# CurrentSenseTest_SCH.net
KiCad netlist of a schematic drawn in Altium Designer
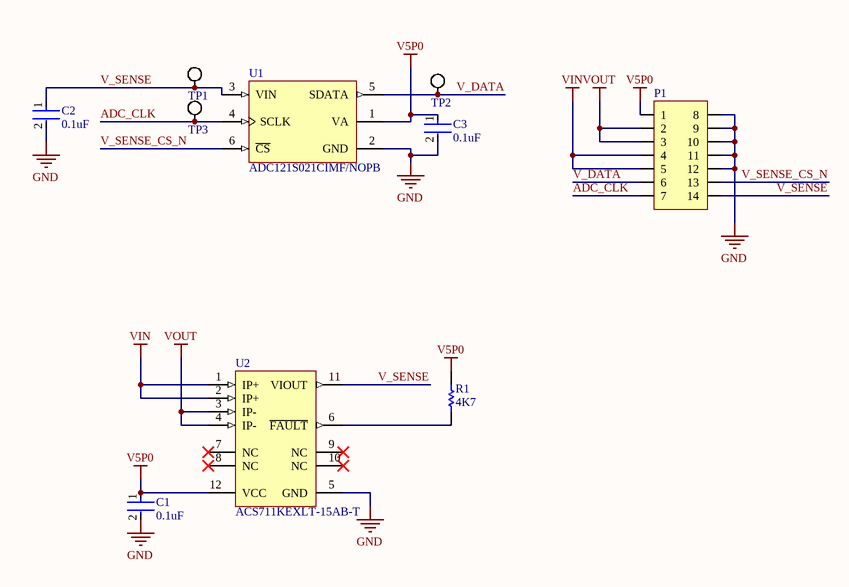
[diagram p0: CurrentSenseTest_SCH.SchDoc]

(export (version "E")
  (design (tool "Eeschema 10.0.6"))
  (components
    (comp (ref "C1")
      (value "0.1uF")
      (footprint "0603")
      (description "CC0603KRX7R9BB104-CAP CER 0.1UF 50V X7R 0603")
      (fields (field (name "MANUFACTURER") "YAGEO") (field (name "VOLTAGE") "50 V"))
      (libsource (lib "TAUV-Lib") (part "0.1uF 0603"))
    )
    (comp (ref "C2")
      (value "0.1uF")
      (footprint "0603")
      (description "CC0603KRX7R9BB104-CAP CER 0.1UF 50V X7R 0603")
      (fields (field (name "MANUFACTURER") "YAGEO") (field (name "VOLTAGE") "50 V"))
      (libsource (lib "TAUV-Lib") (part "0.1uF 0603"))
    )
    (comp (ref "C3")
      (value "0.1uF")
      (footprint "0603")
      (description "CC0603KRX7R9BB104-CAP CER 0.1UF 50V X7R 0603")
      (fields (field (name "MANUFACTURER") "YAGEO") (field (name "VOLTAGE") "50 V"))
      (libsource (lib "TAUV-Lib") (part "0.1uF 0603"))
    )
    (comp (ref "P1")
      (value "14-Pin 2-Row Nano-Fit Right Angle")
      (footprint "MOLEX NANO-FIT 2X7 - Right Angle")
      (description "NanoFit Right Hdr TH DR 14Ckt")
      (fields (field (name "PART NUMBER") "105314-1214") (field (name "MANUFACTURER") "Molex"))
      (libsource (lib "TAUV-Lib") (part "14-Pin 2-Row Nano-Fit Right Angle"))
    )
    (comp (ref "R1")
      (value "4K7")
      (footprint "0603")
      (description "4K7 0.1W 1% 0603 (1608 Metric)  SMD")
      (fields (field (name "POWER") "0.1 W") (field (name "TOLERANCE") "1 %"))
      (libsource (lib "TAUV-Lib") (part "4K7 0603"))
    )
    (comp (ref "TP1")
      (value "Test Point Pad")
      (footprint "Test Point Pad")
      (description "Test point, Pad, 30 mil")
      (libsource (lib "TAUV-Lib") (part "Test Point Pad"))
    )
    (comp (ref "TP2")
      (value "Test Point Pad")
      (footprint "Test Point Pad")
      (description "Test point, Pad, 30 mil")
      (libsource (lib "TAUV-Lib") (part "Test Point Pad"))
    )
    (comp (ref "TP3")
      (value "Test Point Pad")
      (footprint "Test Point Pad")
      (description "Test point, Pad, 30 mil")
      (libsource (lib "TAUV-Lib") (part "Test Point Pad"))
    )
    (comp (ref "U1")
      (value "ADC121S021CIMF/NOPB")
      (footprint "MF06A_L")
      (description "Single Channel, 50 to 200 kSPS, 12-Bit A/D Converter, 6-pin SOT-23, Pb-Free")
      (fields (field (name "MANUFACTURER") "National Semiconductor"))
      (libsource (lib "Altium Content Vault") (part "CON-ADC-ADC101S101CIMF"))
    )
    (comp (ref "U2")
      (value "ACS711KEXLT-15AB-T")
      (footprint "ALEG-EX-12_V")
      (libsource (lib "Altium Content Vault") (part "ALEG-ACS711-QFN-12"))
    )
  )
  (nets
    (net (code "1") (name "/ADC_CLK") (class "Default")
      (node (ref "P1") (pin "7") (pinfunction "7_7") (pintype "passive"))
      (node (ref "TP3") (pin "1") (pinfunction "1_1") (pintype "passive"))
      (node (ref "U1") (pin "4") (pinfunction "SCLK_4") (pintype "input"))
    )
    (net (code "2") (name "/V_DATA") (class "Default")
      (node (ref "P1") (pin "6") (pinfunction "6_6") (pintype "passive"))
      (node (ref "TP2") (pin "1") (pinfunction "1_1") (pintype "passive"))
      (node (ref "U1") (pin "5") (pinfunction "SDATA_5") (pintype "output"))
    )
    (net (code "3") (name "/V_SENSE") (class "Default")
      (node (ref "C2") (pin "1") (pinfunction "1_1") (pintype "passive"))
      (node (ref "P1") (pin "14") (pinfunction "14_14") (pintype "passive"))
      (node (ref "TP1") (pin "1") (pinfunction "1_1") (pintype "passive"))
      (node (ref "U1") (pin "3") (pinfunction "VIN_3") (pintype "input"))
      (node (ref "U2") (pin "11") (pinfunction "VIOUT_11") (pintype "output"))
    )
    (net (code "4") (name "/V_SENSE_CS_N") (class "Default")
      (node (ref "P1") (pin "13") (pinfunction "13_13") (pintype "passive"))
      (node (ref "U1") (pin "6") (pinfunction "~{CS}_6") (pintype "input"))
    )
    (net (code "5") (name "GND") (class "Default")
      (node (ref "C1") (pin "2") (pinfunction "2_2") (pintype "passive"))
      (node (ref "C2") (pin "2") (pinfunction "2_2") (pintype "passive"))
      (node (ref "C3") (pin "2") (pinfunction "2_2") (pintype "passive"))
      (node (ref "P1") (pin "10") (pinfunction "10_10") (pintype "passive"))
      (node (ref "P1") (pin "11") (pinfunction "11_11") (pintype "passive"))
      (node (ref "P1") (pin "12") (pinfunction "12_12") (pintype "passive"))
      (node (ref "P1") (pin "8") (pinfunction "8_8") (pintype "passive"))
      (node (ref "P1") (pin "9") (pinfunction "9_9") (pintype "passive"))
      (node (ref "U1") (pin "2") (pinfunction "GND_2") (pintype "power_in"))
      (node (ref "U2") (pin "5") (pinfunction "GND_5") (pintype "power_in"))
    )
    (net (code "6") (name "Net-(U2-~{FAULT})") (class "Default")
      (node (ref "R1") (pin "2") (pinfunction "2_2") (pintype "passive"))
      (node (ref "U2") (pin "6") (pinfunction "~{FAULT}_6") (pintype "output"))
    )
    (net (code "7") (name "V5P0") (class "Default")
      (node (ref "C1") (pin "1") (pinfunction "1_1") (pintype "passive"))
      (node (ref "C3") (pin "1") (pinfunction "1_1") (pintype "passive"))
      (node (ref "P1") (pin "1") (pinfunction "1_1") (pintype "passive"))
      (node (ref "R1") (pin "1") (pinfunction "1_1") (pintype "passive"))
      (node (ref "U1") (pin "1") (pinfunction "VA_1") (pintype "power_in"))
      (node (ref "U2") (pin "12") (pinfunction "VCC_12") (pintype "power_in"))
    )
    (net (code "8") (name "VIN") (class "Default")
      (node (ref "P1") (pin "4") (pinfunction "4_4") (pintype "passive"))
      (node (ref "P1") (pin "5") (pinfunction "5_5") (pintype "passive"))
      (node (ref "U2") (pin "1") (pinfunction "IP+_1") (pintype "input"))
      (node (ref "U2") (pin "2") (pinfunction "IP+_2") (pintype "input"))
    )
    (net (code "9") (name "VOUT") (class "Default")
      (node (ref "P1") (pin "2") (pinfunction "2_2") (pintype "passive"))
      (node (ref "P1") (pin "3") (pinfunction "3_3") (pintype "passive"))
      (node (ref "U2") (pin "3") (pinfunction "IP-_3") (pintype "input"))
      (node (ref "U2") (pin "4") (pinfunction "IP-_4") (pintype "input"))
    )
    (net (code "10") (name "unconnected-(U2-NC-Pad7)") (class "Default")
      (node (ref "U2") (pin "7") (pinfunction "NC_7") (pintype "passive+no_connect"))
    )
    (net (code "11") (name "unconnected-(U2-NC-Pad8)") (class "Default")
      (node (ref "U2") (pin "8") (pinfunction "NC_8") (pintype "passive+no_connect"))
    )
    (net (code "12") (name "unconnected-(U2-NC-Pad9)") (class "Default")
      (node (ref "U2") (pin "9") (pinfunction "NC_9") (pintype "passive+no_connect"))
    )
    (net (code "13") (name "unconnected-(U2-NC-Pad10)") (class "Default")
      (node (ref "U2") (pin "10") (pinfunction "NC_10") (pintype "passive+no_connect"))
    )
  )
)
